# triangulator-lm324.net
KiCad netlist of a schematic drawn in EAGLE
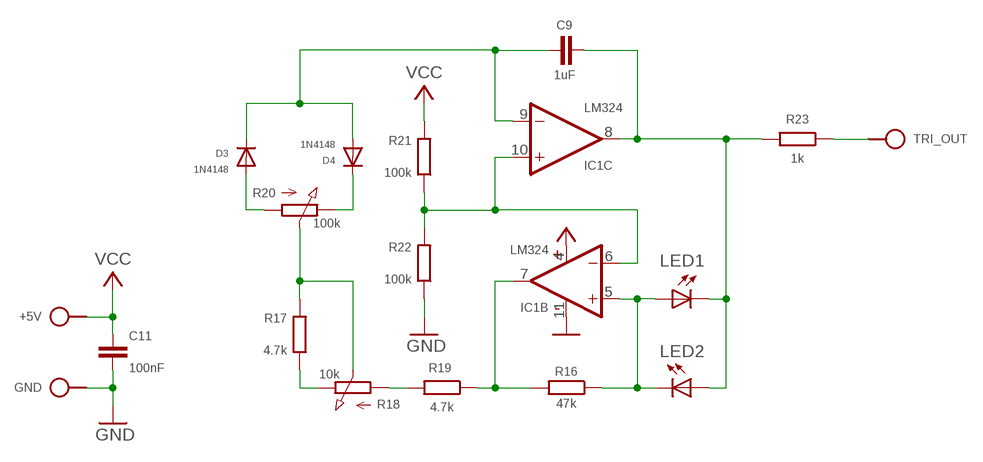
[diagram p0: schematic, sheet 1]

(export (version "E")
  (design (tool "Eeschema 10.0.6"))
  (components
    (comp (ref "+5V")
      (value "VCC")
      (footprint "eagle-import:SPAD")
      (libsource (lib "eagle-import") (part "SPAD"))
    )
    (comp (ref "C9")
      (value "1uF")
      (footprint "eagle-import:C050-024X044_V")
      (libsource (lib "eagle-import") (part "C050-024X044/V"))
    )
    (comp (ref "C11")
      (value "100nF")
      (footprint "eagle-import:C050-020X036")
      (libsource (lib "eagle-import") (part "C050-020X036"))
    )
    (comp (ref "D3")
      (value "1N4148")
      (footprint "eagle-import:DO34-7V")
      (libsource (lib "eagle-import") (part "1N414834-7V"))
    )
    (comp (ref "D4")
      (value "1N4148")
      (footprint "eagle-import:DO34-7V")
      (libsource (lib "eagle-import") (part "1N414834-7V"))
    )
    (comp (ref "GND")
      (value "GND")
      (footprint "eagle-import:SPAD")
      (libsource (lib "eagle-import") (part "SPAD"))
    )
    (comp (ref "IC1")
      (value "LM324")
      (footprint "eagle-import:DIL14")
      (libsource (lib "eagle-import") (part "LM324N"))
    )
    (comp (ref "LED1")
      (value "LED3MM")
      (footprint "eagle-import:LED3MM")
      (libsource (lib "eagle-import") (part "LED3MM"))
    )
    (comp (ref "LED2")
      (value "LED3MM")
      (footprint "eagle-import:LED3MM")
      (libsource (lib "eagle-import") (part "LED3MM"))
    )
    (comp (ref "R16")
      (value "47k")
      (footprint "eagle-import:0202_7-V")
      (libsource (lib "eagle-import") (part "R0202/7-V"))
    )
    (comp (ref "R17")
      (value "4.7k")
      (footprint "eagle-import:0202_7")
      (libsource (lib "eagle-import") (part "R0202/7"))
    )
    (comp (ref "R18")
      (value "10k")
      (footprint "eagle-import:POT")
      (libsource (lib "eagle-import") (part "POT"))
    )
    (comp (ref "R19")
      (value "4.7k")
      (footprint "eagle-import:0202_7-V")
      (libsource (lib "eagle-import") (part "R0202/7-V"))
    )
    (comp (ref "R20")
      (value "100k")
      (footprint "eagle-import:POT")
      (libsource (lib "eagle-import") (part "POT"))
    )
    (comp (ref "R21")
      (value "100k")
      (footprint "eagle-import:0202_7-V")
      (libsource (lib "eagle-import") (part "R0202/7-V"))
    )
    (comp (ref "R22")
      (value "100k")
      (footprint "eagle-import:0202_7-V")
      (libsource (lib "eagle-import") (part "R0202/7-V"))
    )
    (comp (ref "R23")
      (value "1k")
      (footprint "eagle-import:0202_7-V")
      (libsource (lib "eagle-import") (part "R0202/7-V"))
    )
    (comp (ref "TRI_OUT")
      (value "TRIANGLE")
      (footprint "eagle-import:SPAD")
      (libsource (lib "eagle-import") (part "SPAD"))
    )
  )
  (nets
    (net (code "1") (name "GND") (class "Default")
      (node (ref "C11") (pin "2") (pinfunction "2_2") (pintype "passive"))
      (node (ref "GND") (pin "1") (pinfunction "P$1_1") (pintype "bidirectional"))
      (node (ref "IC1") (pin "11") (pinfunction "V-_11") (pintype "power_in"))
      (node (ref "R22") (pin "1") (pinfunction "1_1") (pintype "passive"))
    )
    (net (code "2") (name "Net-(IC1B-+IN)") (class "Default")
      (node (ref "IC1") (pin "5") (pinfunction "+IN_5") (pintype "input"))
      (node (ref "LED1") (pin "A") (pinfunction "A_A") (pintype "passive"))
      (node (ref "LED2") (pin "K") (pinfunction "C_K") (pintype "passive"))
      (node (ref "R16") (pin "1") (pinfunction "1_1") (pintype "passive"))
    )
    (net (code "3") (name "Net-(IC1B--IN)") (class "Default")
      (node (ref "IC1") (pin "10") (pinfunction "+IN_10") (pintype "input"))
      (node (ref "IC1") (pin "6") (pinfunction "-IN_6") (pintype "input"))
      (node (ref "R21") (pin "1") (pinfunction "1_1") (pintype "passive"))
      (node (ref "R22") (pin "2") (pinfunction "2_2") (pintype "passive"))
    )
    (net (code "4") (name "Net-(IC1B-OUT)") (class "Default")
      (node (ref "IC1") (pin "7") (pinfunction "OUT_7") (pintype "output"))
      (node (ref "R16") (pin "2") (pinfunction "2_2") (pintype "passive"))
      (node (ref "R19") (pin "1") (pinfunction "1_1") (pintype "passive"))
    )
    (net (code "5") (name "Net-(IC1C--IN)") (class "Default")
      (node (ref "C9") (pin "1") (pinfunction "1_1") (pintype "passive"))
      (node (ref "D3") (pin "C") (pinfunction "C_C") (pintype "passive"))
      (node (ref "D4") (pin "A") (pinfunction "A_A") (pintype "passive"))
      (node (ref "IC1") (pin "9") (pinfunction "-IN_9") (pintype "input"))
    )
    (net (code "6") (name "Net-(IC1C-OUT)") (class "Default")
      (node (ref "C9") (pin "2") (pinfunction "2_2") (pintype "passive"))
      (node (ref "IC1") (pin "8") (pinfunction "OUT_8") (pintype "output"))
      (node (ref "LED1") (pin "K") (pinfunction "C_K") (pintype "passive"))
      (node (ref "LED2") (pin "A") (pinfunction "A_A") (pintype "passive"))
      (node (ref "R23") (pin "2") (pinfunction "2_2") (pintype "passive"))
    )
    (net (code "7") (name "Net-(R18-A)") (class "Default")
      (node (ref "R18") (pin "1") (pinfunction "A_1") (pintype "passive"))
      (node (ref "R19") (pin "2") (pinfunction "2_2") (pintype "passive"))
    )
    (net (code "8") (name "Net-(R18-E)") (class "Default")
      (node (ref "R17") (pin "1") (pinfunction "1_1") (pintype "passive"))
      (node (ref "R18") (pin "3") (pinfunction "E_3") (pintype "passive"))
    )
    (net (code "9") (name "Net-(R18-S)") (class "Default")
      (node (ref "R17") (pin "2") (pinfunction "2_2") (pintype "passive"))
      (node (ref "R18") (pin "2") (pinfunction "S_2") (pintype "passive"))
      (node (ref "R20") (pin "2") (pinfunction "S_2") (pintype "passive"))
    )
    (net (code "10") (name "Net-(R20-A)") (class "Default")
      (node (ref "D3") (pin "A") (pinfunction "A_A") (pintype "passive"))
      (node (ref "R20") (pin "1") (pinfunction "A_1") (pintype "passive"))
    )
    (net (code "11") (name "Net-(R20-E)") (class "Default")
      (node (ref "D4") (pin "C") (pinfunction "C_C") (pintype "passive"))
      (node (ref "R20") (pin "3") (pinfunction "E_3") (pintype "passive"))
    )
    (net (code "12") (name "Net-(TRI_OUT-P$1)") (class "Default")
      (node (ref "R23") (pin "1") (pinfunction "1_1") (pintype "passive"))
      (node (ref "TRI_OUT") (pin "1") (pinfunction "P$1_1") (pintype "bidirectional"))
    )
    (net (code "13") (name "VCC") (class "Default")
      (node (ref "+5V") (pin "1") (pinfunction "P$1_1") (pintype "bidirectional"))
      (node (ref "C11") (pin "1") (pinfunction "1_1") (pintype "passive"))
      (node (ref "IC1") (pin "4") (pinfunction "V+_4") (pintype "power_in"))
      (node (ref "R21") (pin "2") (pinfunction "2_2") (pintype "passive"))
    )
  )
)
